# I2C_switch.net
KiCad netlist of a schematic drawn in Altium Designer
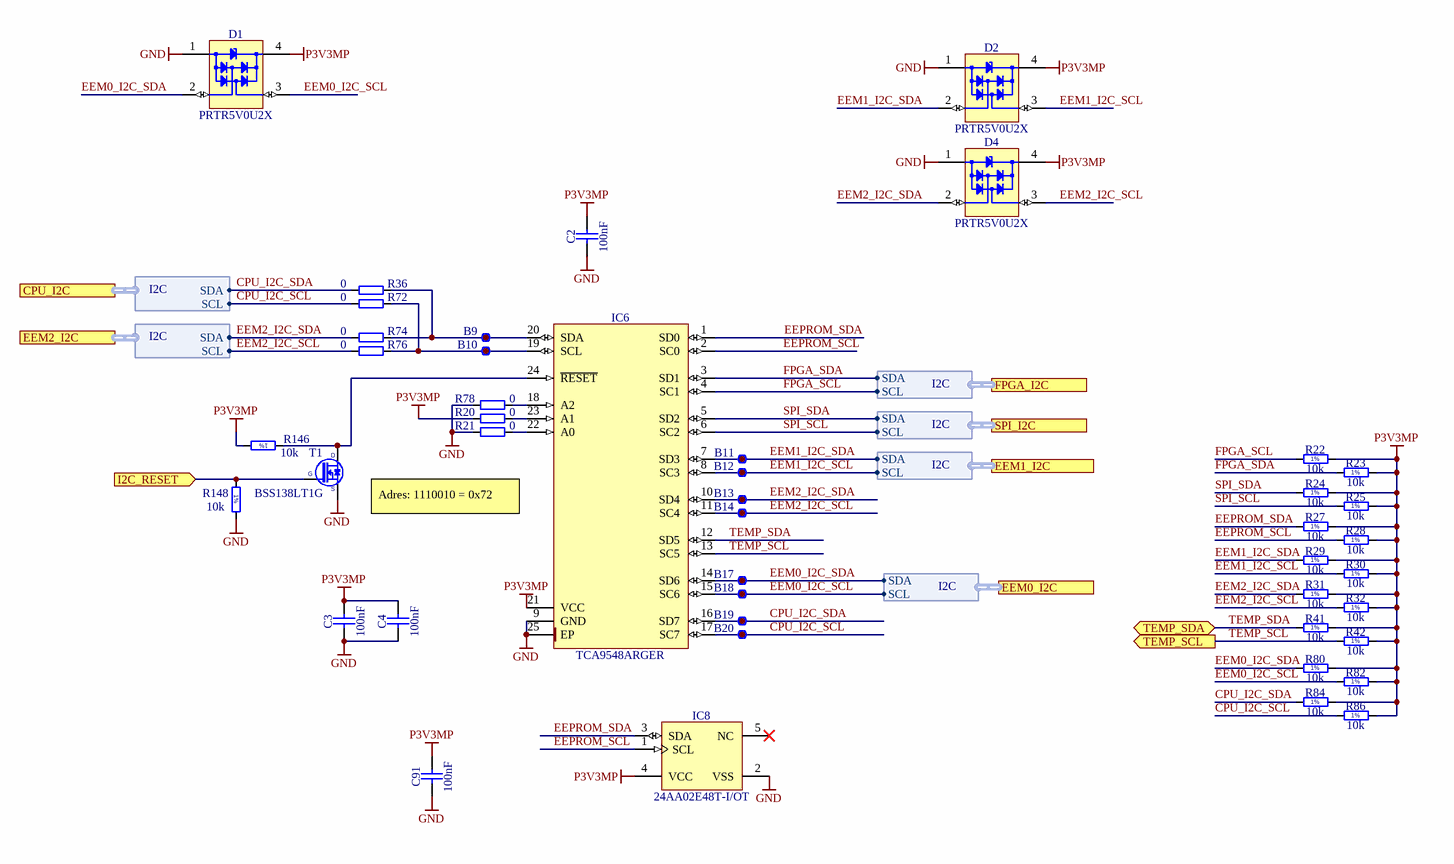
[diagram p0: I2C_switch.SchDoc]

(export (version "E")
  (design (tool "Eeschema 10.0.6"))
  (components
    (comp (ref "B9")
      (value "SMD Pad")
      (footprint "C100")
      (description "Through Hole Pad")
      (fields (field (name "PART NUMBER") "SMD_PAD_D1MM") (field (name "AUTHOR") "CERN DEM JLC"))
      (libsource (lib "Eletro-mechanical") (part "Single SMD Pad (Round)"))
    )
    (comp (ref "B10")
      (value "SMD Pad")
      (footprint "C100")
      (description "Through Hole Pad")
      (fields (field (name "PART NUMBER") "SMD_PAD_D1MM") (field (name "AUTHOR") "CERN DEM JLC"))
      (libsource (lib "Eletro-mechanical") (part "Single SMD Pad (Round)"))
    )
    (comp (ref "B11")
      (value "SMD Pad")
      (footprint "C100")
      (description "Through Hole Pad")
      (fields (field (name "PART NUMBER") "SMD_PAD_D1MM") (field (name "AUTHOR") "CERN DEM JLC"))
      (libsource (lib "Eletro-mechanical") (part "Single SMD Pad (Round)"))
    )
    (comp (ref "B12")
      (value "SMD Pad")
      (footprint "C100")
      (description "Through Hole Pad")
      (fields (field (name "PART NUMBER") "SMD_PAD_D1MM") (field (name "AUTHOR") "CERN DEM JLC"))
      (libsource (lib "Eletro-mechanical") (part "Single SMD Pad (Round)"))
    )
    (comp (ref "B13")
      (value "SMD Pad")
      (footprint "C100")
      (description "Through Hole Pad")
      (fields (field (name "PART NUMBER") "SMD_PAD_D1MM") (field (name "AUTHOR") "CERN DEM JLC"))
      (libsource (lib "Eletro-mechanical") (part "Single SMD Pad (Round)"))
    )
    (comp (ref "B14")
      (value "SMD Pad")
      (footprint "C100")
      (description "Through Hole Pad")
      (fields (field (name "PART NUMBER") "SMD_PAD_D1MM") (field (name "AUTHOR") "CERN DEM JLC"))
      (libsource (lib "Eletro-mechanical") (part "Single SMD Pad (Round)"))
    )
    (comp (ref "B17")
      (value "SMD Pad")
      (footprint "C100")
      (description "Through Hole Pad")
      (fields (field (name "PART NUMBER") "SMD_PAD_D1MM") (field (name "AUTHOR") "CERN DEM JLC"))
      (libsource (lib "Eletro-mechanical") (part "Single SMD Pad (Round)"))
    )
    (comp (ref "B18")
      (value "SMD Pad")
      (footprint "C100")
      (description "Through Hole Pad")
      (fields (field (name "PART NUMBER") "SMD_PAD_D1MM") (field (name "AUTHOR") "CERN DEM JLC"))
      (libsource (lib "Eletro-mechanical") (part "Single SMD Pad (Round)"))
    )
    (comp (ref "B19")
      (value "SMD Pad")
      (footprint "C100")
      (description "Through Hole Pad")
      (fields (field (name "PART NUMBER") "SMD_PAD_D1MM") (field (name "AUTHOR") "CERN DEM JLC"))
      (libsource (lib "Eletro-mechanical") (part "Single SMD Pad (Round)"))
    )
    (comp (ref "B20")
      (value "SMD Pad")
      (footprint "C100")
      (description "Through Hole Pad")
      (fields (field (name "PART NUMBER") "SMD_PAD_D1MM") (field (name "AUTHOR") "CERN DEM JLC"))
      (libsource (lib "Eletro-mechanical") (part "Single SMD Pad (Round)"))
    )
    (comp (ref "C2")
      (value "100nF")
      (footprint "CAPC1005X55N")
      (description "Non-polarised capacitor")
      (fields
        (field (name "PART NUMBER") "CC0402_100NF_16V_10%_X5R")
        (field (name "VOLTAGE") "16V")
        (field (name "AUTHOR") "CERN DEM JLC")
      )
      (libsource (lib "Capacitors") (part "Capacitor - non polarized"))
    )
    (comp (ref "C3")
      (value "100nF")
      (footprint "CAPC1005X55N")
      (description "Non-polarised capacitor")
      (fields
        (field (name "PART NUMBER") "CC0402_100NF_16V_10%_X5R")
        (field (name "VOLTAGE") "16V")
        (field (name "AUTHOR") "CERN DEM JLC")
      )
      (libsource (lib "Capacitors") (part "Capacitor - non polarized"))
    )
    (comp (ref "C4")
      (value "100nF")
      (footprint "CAPC1005X55N")
      (description "Non-polarised capacitor")
      (fields
        (field (name "PART NUMBER") "CC0402_100NF_16V_10%_X5R")
        (field (name "VOLTAGE") "16V")
        (field (name "AUTHOR") "CERN DEM JLC")
      )
      (libsource (lib "Capacitors") (part "Capacitor - non polarized"))
    )
    (comp (ref "C91")
      (value "100nF")
      (footprint "CAPC1005X55N")
      (description "Non-polarised capacitor")
      (fields
        (field (name "PART NUMBER") "CC0402_100NF_16V_10%_X5R")
        (field (name "VOLTAGE") "16V")
        (field (name "AUTHOR") "CERN DEM JLC")
      )
      (libsource (lib "Capacitors") (part "Capacitor - non polarized"))
    )
    (comp (ref "D1")
      (value "PRTR5V0U2X")
      (footprint "SOT190P230X110-4N")
      (description "Ultra Low Capacitance Double Rail-to-Rail ESD Protection Diode")
      (fields
        (field (name "VOLTAGE") "5.5V")
        (field (name "MANUFACTURER") "NXP SEMICONDUCTORS")
        (field (name "AUTHOR") "CERN DEM JLC")
      )
      (libsource (lib "ICs And Semiconductors") (part "PRTR5V0U2X"))
    )
    (comp (ref "D2")
      (value "PRTR5V0U2X")
      (footprint "SOT190P230X110-4N")
      (description "Ultra Low Capacitance Double Rail-to-Rail ESD Protection Diode")
      (fields
        (field (name "VOLTAGE") "5.5V")
        (field (name "MANUFACTURER") "NXP SEMICONDUCTORS")
        (field (name "AUTHOR") "CERN DEM JLC")
      )
      (libsource (lib "ICs And Semiconductors") (part "PRTR5V0U2X"))
    )
    (comp (ref "D4")
      (value "PRTR5V0U2X")
      (footprint "SOT190P230X110-4N")
      (description "Ultra Low Capacitance Double Rail-to-Rail ESD Protection Diode")
      (fields
        (field (name "VOLTAGE") "5.5V")
        (field (name "MANUFACTURER") "NXP SEMICONDUCTORS")
        (field (name "AUTHOR") "CERN DEM JLC")
      )
      (libsource (lib "ICs And Semiconductors") (part "PRTR5V0U2X"))
    )
    (comp (ref "IC6")
      (value "TCA9548ARGER")
      (footprint "QFN50P400X400X100-25N-S220")
      (description "Low Voltage 8-Channel I2C Switch With Reset")
      (fields (field (name "MANUFACTURER") "TEXAS INSTRUMENTS") (field (name "AUTHOR") "CERN DEM JLC"))
      (libsource (lib "ICs And Semiconductors") (part "TCA9548ARGER"))
    )
    (comp (ref "IC8")
      (value "24AA02E48T-I/OT")
      (footprint "SOT95P280X145-5N")
      (description "1.7V-5.5V, 2K I2C Serial EEPROM With EUI-48 Node Identity")
      (fields (field (name "MANUFACTURER") "MICROCHIP TECHNOLOGY") (field (name "AUTHOR") "CERN DEM MR"))
      (libsource (lib "ICs And Semiconductors") (part "24AA02E48T-I/OT"))
    )
    (comp (ref "R20")
      (value "0")
      (footprint "RESC1005X40N")
      (description "Resistor")
      (fields
        (field (name "PART NUMBER") "R0402_0R_JUMPER")
        (field (name "MANUFACTURER") "GENERIC")
        (field (name "AUTHOR") "CERN DEM JLC")
      )
      (libsource (lib "Resistors") (part "Resistor"))
    )
    (comp (ref "R21")
      (value "0")
      (footprint "RESC1005X40N")
      (description "Resistor")
      (fields
        (field (name "PART NUMBER") "R0402_0R_JUMPER")
        (field (name "MANUFACTURER") "GENERIC")
        (field (name "AUTHOR") "CERN DEM JLC")
      )
      (libsource (lib "Resistors") (part "Resistor"))
    )
    (comp (ref "R22")
      (value "10k")
      (footprint "RESC1005X40N")
      (description "Resistor - 1%")
      (fields
        (field (name "PART NUMBER") "R0402_10K_1%_0.0625W_100PPM")
        (field (name "POWER") "0.0625W")
        (field (name "AUTHOR") "CERN DEM JLC")
      )
      (libsource (lib "Resistors") (part "Resistor - 1%"))
    )
    (comp (ref "R23")
      (value "10k")
      (footprint "RESC1005X40N")
      (description "Resistor - 1%")
      (fields
        (field (name "PART NUMBER") "R0402_10K_1%_0.0625W_100PPM")
        (field (name "POWER") "0.0625W")
        (field (name "AUTHOR") "CERN DEM JLC")
      )
      (libsource (lib "Resistors") (part "Resistor - 1%"))
    )
    (comp (ref "R24")
      (value "10k")
      (footprint "RESC1005X40N")
      (description "Resistor - 1%")
      (fields
        (field (name "PART NUMBER") "R0402_10K_1%_0.0625W_100PPM")
        (field (name "POWER") "0.0625W")
        (field (name "AUTHOR") "CERN DEM JLC")
      )
      (libsource (lib "Resistors") (part "Resistor - 1%"))
    )
    (comp (ref "R25")
      (value "10k")
      (footprint "RESC1005X40N")
      (description "Resistor - 1%")
      (fields
        (field (name "PART NUMBER") "R0402_10K_1%_0.0625W_100PPM")
        (field (name "POWER") "0.0625W")
        (field (name "AUTHOR") "CERN DEM JLC")
      )
      (libsource (lib "Resistors") (part "Resistor - 1%"))
    )
    (comp (ref "R27")
      (value "10k")
      (footprint "RESC1005X40N")
      (description "Resistor - 1%")
      (fields
        (field (name "PART NUMBER") "R0402_10K_1%_0.0625W_100PPM")
        (field (name "POWER") "0.0625W")
        (field (name "AUTHOR") "CERN DEM JLC")
      )
      (libsource (lib "Resistors") (part "Resistor - 1%"))
    )
    (comp (ref "R28")
      (value "10k")
      (footprint "RESC1005X40N")
      (description "Resistor - 1%")
      (fields
        (field (name "PART NUMBER") "R0402_10K_1%_0.0625W_100PPM")
        (field (name "POWER") "0.0625W")
        (field (name "AUTHOR") "CERN DEM JLC")
      )
      (libsource (lib "Resistors") (part "Resistor - 1%"))
    )
    (comp (ref "R29")
      (value "10k")
      (footprint "RESC1005X40N")
      (description "Resistor - 1%")
      (fields
        (field (name "PART NUMBER") "R0402_10K_1%_0.0625W_100PPM")
        (field (name "POWER") "0.0625W")
        (field (name "AUTHOR") "CERN DEM JLC")
      )
      (libsource (lib "Resistors") (part "Resistor - 1%"))
    )
    (comp (ref "R30")
      (value "10k")
      (footprint "RESC1005X40N")
      (description "Resistor - 1%")
      (fields
        (field (name "PART NUMBER") "R0402_10K_1%_0.0625W_100PPM")
        (field (name "POWER") "0.0625W")
        (field (name "AUTHOR") "CERN DEM JLC")
      )
      (libsource (lib "Resistors") (part "Resistor - 1%"))
    )
    (comp (ref "R31")
      (value "10k")
      (footprint "RESC1005X40N")
      (description "Resistor - 1%")
      (fields
        (field (name "PART NUMBER") "R0402_10K_1%_0.0625W_100PPM")
        (field (name "POWER") "0.0625W")
        (field (name "AUTHOR") "CERN DEM JLC")
      )
      (libsource (lib "Resistors") (part "Resistor - 1%"))
    )
    (comp (ref "R32")
      (value "10k")
      (footprint "RESC1005X40N")
      (description "Resistor - 1%")
      (fields
        (field (name "PART NUMBER") "R0402_10K_1%_0.0625W_100PPM")
        (field (name "POWER") "0.0625W")
        (field (name "AUTHOR") "CERN DEM JLC")
      )
      (libsource (lib "Resistors") (part "Resistor - 1%"))
    )
    (comp (ref "R36")
      (value "0")
      (footprint "RESC1608X55N")
      (description "Resistor")
      (fields
        (field (name "PART NUMBER") "R0603_0R_JUMPER")
        (field (name "MANUFACTURER") "GENERIC")
        (field (name "AUTHOR") "CERN DEM JLC")
      )
      (libsource (lib "Resistors") (part "Resistor"))
    )
    (comp (ref "R41")
      (value "10k")
      (footprint "RESC1005X40N")
      (description "Resistor - 1%")
      (fields
        (field (name "PART NUMBER") "R0402_10K_1%_0.0625W_100PPM")
        (field (name "POWER") "0.0625W")
        (field (name "AUTHOR") "CERN DEM JLC")
      )
      (libsource (lib "Resistors") (part "Resistor - 1%"))
    )
    (comp (ref "R42")
      (value "10k")
      (footprint "RESC1005X40N")
      (description "Resistor - 1%")
      (fields
        (field (name "PART NUMBER") "R0402_10K_1%_0.0625W_100PPM")
        (field (name "POWER") "0.0625W")
        (field (name "AUTHOR") "CERN DEM JLC")
      )
      (libsource (lib "Resistors") (part "Resistor - 1%"))
    )
    (comp (ref "R72")
      (value "0")
      (footprint "RESC1608X55N")
      (description "Resistor")
      (fields
        (field (name "PART NUMBER") "R0603_0R_JUMPER")
        (field (name "MANUFACTURER") "GENERIC")
        (field (name "AUTHOR") "CERN DEM JLC")
      )
      (libsource (lib "Resistors") (part "Resistor"))
    )
    (comp (ref "R74")
      (value "0")
      (footprint "RESC1608X55N")
      (description "Resistor")
      (fields
        (field (name "PART NUMBER") "R0603_0R_JUMPER")
        (field (name "MANUFACTURER") "GENERIC")
        (field (name "AUTHOR") "CERN DEM JLC")
      )
      (libsource (lib "Resistors") (part "Resistor"))
    )
    (comp (ref "R76")
      (value "0")
      (footprint "RESC1608X55N")
      (description "Resistor")
      (fields
        (field (name "PART NUMBER") "R0603_0R_JUMPER")
        (field (name "MANUFACTURER") "GENERIC")
        (field (name "AUTHOR") "CERN DEM JLC")
      )
      (libsource (lib "Resistors") (part "Resistor"))
    )
    (comp (ref "R78")
      (value "0")
      (footprint "RESC1005X40N")
      (description "Resistor")
      (fields
        (field (name "PART NUMBER") "R0402_0R_JUMPER")
        (field (name "MANUFACTURER") "GENERIC")
        (field (name "AUTHOR") "CERN DEM JLC")
      )
      (libsource (lib "Resistors") (part "Resistor"))
    )
    (comp (ref "R80")
      (value "10k")
      (footprint "RESC1005X40N")
      (description "Resistor - 1%")
      (fields
        (field (name "PART NUMBER") "R0402_10K_1%_0.0625W_100PPM")
        (field (name "POWER") "0.0625W")
        (field (name "AUTHOR") "CERN DEM JLC")
      )
      (libsource (lib "Resistors") (part "Resistor - 1%"))
    )
    (comp (ref "R82")
      (value "10k")
      (footprint "RESC1005X40N")
      (description "Resistor - 1%")
      (fields
        (field (name "PART NUMBER") "R0402_10K_1%_0.0625W_100PPM")
        (field (name "POWER") "0.0625W")
        (field (name "AUTHOR") "CERN DEM JLC")
      )
      (libsource (lib "Resistors") (part "Resistor - 1%"))
    )
    (comp (ref "R84")
      (value "10k")
      (footprint "RESC1005X40N")
      (description "Resistor - 1%")
      (fields
        (field (name "PART NUMBER") "R0402_10K_1%_0.0625W_100PPM")
        (field (name "POWER") "0.0625W")
        (field (name "AUTHOR") "CERN DEM JLC")
      )
      (libsource (lib "Resistors") (part "Resistor - 1%"))
    )
    (comp (ref "R86")
      (value "10k")
      (footprint "RESC1005X40N")
      (description "Resistor - 1%")
      (fields
        (field (name "PART NUMBER") "R0402_10K_1%_0.0625W_100PPM")
        (field (name "POWER") "0.0625W")
        (field (name "AUTHOR") "CERN DEM JLC")
      )
      (libsource (lib "Resistors") (part "Resistor - 1%"))
    )
    (comp (ref "R146")
      (value "10k")
      (footprint "RESC1005X40N")
      (description "Resistor - 1%")
      (fields
        (field (name "PART NUMBER") "R0402_10K_1%_0.0625W_100PPM")
        (field (name "POWER") "0.0625W")
        (field (name "AUTHOR") "CERN DEM JLC")
      )
      (libsource (lib "Resistors") (part "Resistor - 1%"))
    )
    (comp (ref "R148")
      (value "10k")
      (footprint "RESC1005X40N")
      (description "Resistor - 1%")
      (fields
        (field (name "PART NUMBER") "R0402_10K_1%_0.0625W_100PPM")
        (field (name "POWER") "0.0625W")
        (field (name "AUTHOR") "CERN DEM JLC")
      )
      (libsource (lib "Resistors") (part "Resistor - 1%"))
    )
    (comp (ref "T1")
      (value "BSS138LT1G")
      (footprint "SOT95P240X110-3N")
      (description "N-CHANNEL MOSFET WITH DIODE")
      (fields (field (name "MANUFACTURER") "ON SEMICONDUCTOR") (field (name "AUTHOR") "CERN DEM JLC"))
      (libsource (lib "ICs And Semiconductors") (part "N-MOSFET-D 1G 2S 3D"))
    )
  )
  (nets
    (net (code "2") (name "/CPU_I2C_SCL") (class "Default")
      (node (ref "B20") (pin "1") (pinfunction "1_1") (pintype "bidirectional"))
      (node (ref "IC6") (pin "17") (pinfunction "SC7_17") (pintype "bidirectional"))
      (node (ref "R72") (pin "1") (pinfunction "1_1") (pintype "passive"))
      (node (ref "R86") (pin "1") (pinfunction "1_1") (pintype "passive"))
    )
    (net (code "3") (name "/CPU_I2C_SDA") (class "Default")
      (node (ref "B19") (pin "1") (pinfunction "1_1") (pintype "bidirectional"))
      (node (ref "IC6") (pin "16") (pinfunction "SD7_16") (pintype "bidirectional"))
      (node (ref "R36") (pin "1") (pinfunction "1_1") (pintype "passive"))
      (node (ref "R84") (pin "1") (pinfunction "1_1") (pintype "passive"))
    )
    (net (code "4") (name "/EEM0_I2C_SCL") (class "Default")
      (node (ref "B18") (pin "1") (pinfunction "1_1") (pintype "bidirectional"))
      (node (ref "D1") (pin "3") (pinfunction "I/O2_3") (pintype "bidirectional"))
      (node (ref "IC6") (pin "15") (pinfunction "SC6_15") (pintype "bidirectional"))
      (node (ref "R82") (pin "1") (pinfunction "1_1") (pintype "passive"))
    )
    (net (code "5") (name "/EEM0_I2C_SDA") (class "Default")
      (node (ref "B17") (pin "1") (pinfunction "1_1") (pintype "bidirectional"))
      (node (ref "D1") (pin "2") (pinfunction "I/O1_2") (pintype "bidirectional"))
      (node (ref "IC6") (pin "14") (pinfunction "SD6_14") (pintype "bidirectional"))
      (node (ref "R80") (pin "1") (pinfunction "1_1") (pintype "passive"))
    )
    (net (code "6") (name "/EEM1_I2C_SCL") (class "Default")
      (node (ref "B12") (pin "1") (pinfunction "1_1") (pintype "bidirectional"))
      (node (ref "D2") (pin "3") (pinfunction "I/O2_3") (pintype "bidirectional"))
      (node (ref "IC6") (pin "8") (pinfunction "SC3_8") (pintype "bidirectional"))
      (node (ref "R30") (pin "1") (pinfunction "1_1") (pintype "passive"))
    )
    (net (code "7") (name "/EEM1_I2C_SDA") (class "Default")
      (node (ref "B11") (pin "1") (pinfunction "1_1") (pintype "bidirectional"))
      (node (ref "D2") (pin "2") (pinfunction "I/O1_2") (pintype "bidirectional"))
      (node (ref "IC6") (pin "7") (pinfunction "SD3_7") (pintype "bidirectional"))
      (node (ref "R29") (pin "1") (pinfunction "1_1") (pintype "passive"))
    )
    (net (code "8") (name "/EEM2_I2C_SCL") (class "Default")
      (node (ref "B14") (pin "1") (pinfunction "1_1") (pintype "bidirectional"))
      (node (ref "D4") (pin "3") (pinfunction "I/O2_3") (pintype "bidirectional"))
      (node (ref "IC6") (pin "11") (pinfunction "SC4_11") (pintype "bidirectional"))
      (node (ref "R32") (pin "1") (pinfunction "1_1") (pintype "passive"))
      (node (ref "R76") (pin "1") (pinfunction "1_1") (pintype "passive"))
    )
    (net (code "9") (name "/EEM2_I2C_SDA") (class "Default")
      (node (ref "B13") (pin "1") (pinfunction "1_1") (pintype "bidirectional"))
      (node (ref "D4") (pin "2") (pinfunction "I/O1_2") (pintype "bidirectional"))
      (node (ref "IC6") (pin "10") (pinfunction "SD4_10") (pintype "bidirectional"))
      (node (ref "R31") (pin "1") (pinfunction "1_1") (pintype "passive"))
      (node (ref "R74") (pin "1") (pinfunction "1_1") (pintype "passive"))
    )
    (net (code "10") (name "/EEPROM_SCL") (class "Default")
      (node (ref "IC6") (pin "2") (pinfunction "SC0_2") (pintype "bidirectional"))
      (node (ref "IC8") (pin "1") (pinfunction "SCL_1") (pintype "input"))
      (node (ref "R28") (pin "1") (pinfunction "1_1") (pintype "passive"))
    )
    (net (code "11") (name "/EEPROM_SDA") (class "Default")
      (node (ref "IC6") (pin "1") (pinfunction "SD0_1") (pintype "bidirectional"))
      (node (ref "IC8") (pin "3") (pinfunction "SDA_3") (pintype "bidirectional"))
      (node (ref "R27") (pin "1") (pinfunction "1_1") (pintype "passive"))
    )
    (net (code "12") (name "/FPGA_SCL") (class "Default")
      (node (ref "IC6") (pin "4") (pinfunction "SC1_4") (pintype "bidirectional"))
      (node (ref "R22") (pin "1") (pinfunction "1_1") (pintype "passive"))
    )
    (net (code "13") (name "/FPGA_SDA") (class "Default")
      (node (ref "IC6") (pin "3") (pinfunction "SD1_3") (pintype "bidirectional"))
      (node (ref "R23") (pin "1") (pinfunction "1_1") (pintype "passive"))
    )
    (net (code "14") (name "/I2C_RESET") (class "Default")
      (node (ref "R148") (pin "1") (pinfunction "1_1") (pintype "passive"))
      (node (ref "T1") (pin "1") (pinfunction "G_1") (pintype "passive"))
    )
    (net (code "15") (name "/SPI_SCL") (class "Default")
      (node (ref "IC6") (pin "6") (pinfunction "SC2_6") (pintype "bidirectional"))
      (node (ref "R25") (pin "1") (pinfunction "1_1") (pintype "passive"))
    )
    (net (code "16") (name "/SPI_SDA") (class "Default")
      (node (ref "IC6") (pin "5") (pinfunction "SD2_5") (pintype "bidirectional"))
      (node (ref "R24") (pin "1") (pinfunction "1_1") (pintype "passive"))
    )
    (net (code "17") (name "/TEMP_SCL") (class "Default")
      (node (ref "IC6") (pin "13") (pinfunction "SC5_13") (pintype "bidirectional"))
      (node (ref "R42") (pin "1") (pinfunction "1_1") (pintype "passive"))
    )
    (net (code "18") (name "/TEMP_SDA") (class "Default")
      (node (ref "IC6") (pin "12") (pinfunction "SD5_12") (pintype "bidirectional"))
      (node (ref "R41") (pin "1") (pinfunction "1_1") (pintype "passive"))
    )
    (net (code "20") (name "GND") (class "Default")
      (node (ref "C2") (pin "1") (pinfunction "1_1") (pintype "passive"))
      (node (ref "C3") (pin "1") (pinfunction "1_1") (pintype "passive"))
      (node (ref "C4") (pin "1") (pinfunction "1_1") (pintype "passive"))
      (node (ref "C91") (pin "1") (pinfunction "1_1") (pintype "passive"))
      (node (ref "D1") (pin "1") (pinfunction "GND_1") (pintype "power_in"))
      (node (ref "D2") (pin "1") (pinfunction "GND_1") (pintype "power_in"))
      (node (ref "D4") (pin "1") (pinfunction "GND_1") (pintype "power_in"))
      (node (ref "IC6") (pin "25") (pinfunction "EP_25") (pintype "power_in"))
      (node (ref "IC6") (pin "9") (pinfunction "GND_9") (pintype "power_in"))
      (node (ref "IC8") (pin "2") (pinfunction "VSS_2") (pintype "power_in"))
      (node (ref "R148") (pin "2") (pinfunction "2_2") (pintype "passive"))
      (node (ref "R21") (pin "1") (pinfunction "1_1") (pintype "passive"))
      (node (ref "R78") (pin "1") (pinfunction "1_1") (pintype "passive"))
      (node (ref "T1") (pin "2") (pinfunction "S_2") (pintype "passive"))
    )
    (net (code "21") (name "Net-(IC6-A0)") (class "Default")
      (node (ref "IC6") (pin "22") (pinfunction "A0_22") (pintype "input"))
      (node (ref "R21") (pin "2") (pinfunction "2_2") (pintype "passive"))
    )
    (net (code "22") (name "Net-(IC6-A1)") (class "Default")
      (node (ref "IC6") (pin "23") (pinfunction "A1_23") (pintype "input"))
      (node (ref "R20") (pin "2") (pinfunction "2_2") (pintype "passive"))
    )
    (net (code "23") (name "Net-(IC6-A2)") (class "Default")
      (node (ref "IC6") (pin "18") (pinfunction "A2_18") (pintype "input"))
      (node (ref "R78") (pin "2") (pinfunction "2_2") (pintype "passive"))
    )
    (net (code "24") (name "Net-(IC6-SCL)") (class "Default")
      (node (ref "B10") (pin "1") (pinfunction "1_1") (pintype "bidirectional"))
      (node (ref "IC6") (pin "19") (pinfunction "SCL_19") (pintype "bidirectional"))
      (node (ref "R72") (pin "2") (pinfunction "2_2") (pintype "passive"))
      (node (ref "R76") (pin "2") (pinfunction "2_2") (pintype "passive"))
    )
    (net (code "25") (name "Net-(IC6-SDA)") (class "Default")
      (node (ref "B9") (pin "1") (pinfunction "1_1") (pintype "bidirectional"))
      (node (ref "IC6") (pin "20") (pinfunction "SDA_20") (pintype "bidirectional"))
      (node (ref "R36") (pin "2") (pinfunction "2_2") (pintype "passive"))
      (node (ref "R74") (pin "2") (pinfunction "2_2") (pintype "passive"))
    )
    (net (code "26") (name "Net-(IC6-~{RESET})") (class "Default")
      (node (ref "IC6") (pin "24") (pinfunction "~{RESET}_24") (pintype "input"))
      (node (ref "R146") (pin "1") (pinfunction "1_1") (pintype "passive"))
      (node (ref "T1") (pin "3") (pinfunction "D_3") (pintype "passive"))
    )
    (net (code "27") (name "P3V3MP") (class "Default")
      (node (ref "C2") (pin "2") (pinfunction "2_2") (pintype "passive"))
      (node (ref "C3") (pin "2") (pinfunction "2_2") (pintype "passive"))
      (node (ref "C4") (pin "2") (pinfunction "2_2") (pintype "passive"))
      (node (ref "C91") (pin "2") (pinfunction "2_2") (pintype "passive"))
      (node (ref "D1") (pin "4") (pinfunction "VCC_4") (pintype "power_in"))
      (node (ref "D2") (pin "4") (pinfunction "VCC_4") (pintype "power_in"))
      (node (ref "D4") (pin "4") (pinfunction "VCC_4") (pintype "power_in"))
      (node (ref "IC6") (pin "21") (pinfunction "VCC_21") (pintype "power_in"))
      (node (ref "IC8") (pin "4") (pinfunction "VCC_4") (pintype "power_in"))
      (node (ref "R146") (pin "2") (pinfunction "2_2") (pintype "passive"))
      (node (ref "R20") (pin "1") (pinfunction "1_1") (pintype "passive"))
      (node (ref "R22") (pin "2") (pinfunction "2_2") (pintype "passive"))
      (node (ref "R23") (pin "2") (pinfunction "2_2") (pintype "passive"))
      (node (ref "R24") (pin "2") (pinfunction "2_2") (pintype "passive"))
      (node (ref "R25") (pin "2") (pinfunction "2_2") (pintype "passive"))
      (node (ref "R27") (pin "2") (pinfunction "2_2") (pintype "passive"))
      (node (ref "R28") (pin "2") (pinfunction "2_2") (pintype "passive"))
      (node (ref "R29") (pin "2") (pinfunction "2_2") (pintype "passive"))
      (node (ref "R30") (pin "2") (pinfunction "2_2") (pintype "passive"))
      (node (ref "R31") (pin "2") (pinfunction "2_2") (pintype "passive"))
      (node (ref "R32") (pin "2") (pinfunction "2_2") (pintype "passive"))
      (node (ref "R41") (pin "2") (pinfunction "2_2") (pintype "passive"))
      (node (ref "R42") (pin "2") (pinfunction "2_2") (pintype "passive"))
      (node (ref "R80") (pin "2") (pinfunction "2_2") (pintype "passive"))
      (node (ref "R82") (pin "2") (pinfunction "2_2") (pintype "passive"))
      (node (ref "R84") (pin "2") (pinfunction "2_2") (pintype "passive"))
      (node (ref "R86") (pin "2") (pinfunction "2_2") (pintype "passive"))
    )
    (net (code "28") (name "unconnected-(IC8-NC-Pad5)") (class "Default")
      (node (ref "IC8") (pin "5") (pinfunction "NC_5") (pintype "passive+no_connect"))
    )
  )
)
